# tag.net
KiCad netlist of a schematic drawn in EAGLE
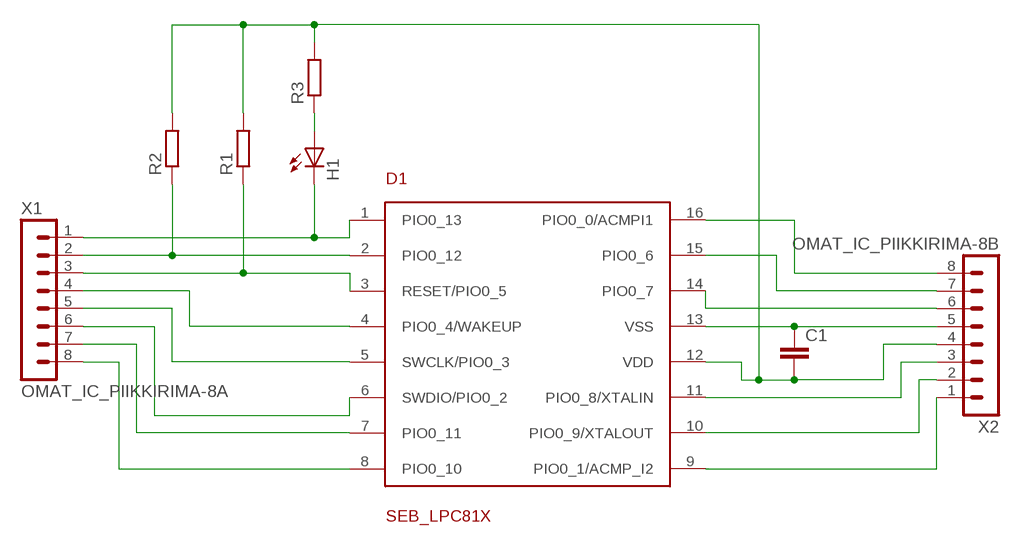
[diagram p0: schematic, sheet 1]

(export (version "E")
  (design (tool "Eeschema 10.0.6"))
  (components
    (comp (ref "C1")
      (value "RCL_C-EUC0603")
      (footprint "eagle-import:RCL_C0603")
      (libsource (lib "eagle-import") (part "RCL_C-EUC0603"))
    )
    (comp (ref "D1")
      (value "SEB_LPC81X")
      (footprint "eagle-import:SEB_TSSOP16")
      (libsource (lib "eagle-import") (part "SEB_LPC81X"))
    )
    (comp (ref "H1")
      (value "OMAT_IC_LEDCHIP-LED0603")
      (footprint "eagle-import:OMAT_IC_CHIP-LED0603")
      (libsource (lib "eagle-import") (part "OMAT_IC_LEDCHIP-LED0603"))
    )
    (comp (ref "R1")
      (value "RCL_R-EU_R0603")
      (footprint "eagle-import:RCL_R0603")
      (libsource (lib "eagle-import") (part "RCL_R-EU_R0603"))
    )
    (comp (ref "R2")
      (value "RCL_R-EU_R0603")
      (footprint "eagle-import:RCL_R0603")
      (libsource (lib "eagle-import") (part "RCL_R-EU_R0603"))
    )
    (comp (ref "R3")
      (value "RCL_R-EU_R0603")
      (footprint "eagle-import:RCL_R0603")
      (libsource (lib "eagle-import") (part "RCL_R-EU_R0603"))
    )
    (comp (ref "X1")
      (value "OMAT_IC_PIIKKIRIMA-8A")
      (footprint "eagle-import:OMAT_IC_PIIKKIRIMA-8")
      (libsource (lib "eagle-import") (part "OMAT_IC_PIIKKIRIMA-8A"))
    )
    (comp (ref "X2")
      (value "OMAT_IC_PIIKKIRIMA-8B")
      (footprint "eagle-import:OMAT_IC_PIIKKIRIMA-8_2")
      (libsource (lib "eagle-import") (part "OMAT_IC_PIIKKIRIMA-8B"))
    )
  )
  (nets
    (net (code "1") (name "Net-(D1-PIO0_0{slash}ACMPI1)") (class "Default")
      (node (ref "D1") (pin "16") (pinfunction "PIO0_0/ACMPI1_16") (pintype "bidirectional"))
      (node (ref "X2") (pin "8") (pinfunction "8_8") (pintype "passive"))
    )
    (net (code "2") (name "Net-(D1-PIO0_1{slash}ACMP_I2)") (class "Default")
      (node (ref "D1") (pin "9") (pinfunction "PIO0_1/ACMP_I2_9") (pintype "bidirectional"))
      (node (ref "X2") (pin "1") (pinfunction "1_1") (pintype "passive"))
    )
    (net (code "3") (name "Net-(D1-PIO0_4{slash}WAKEUP)") (class "Default")
      (node (ref "D1") (pin "4") (pinfunction "PIO0_4/WAKEUP_4") (pintype "bidirectional"))
      (node (ref "X1") (pin "4") (pinfunction "4_4") (pintype "passive"))
    )
    (net (code "4") (name "Net-(D1-PIO0_6)") (class "Default")
      (node (ref "D1") (pin "15") (pinfunction "PIO0_6_15") (pintype "bidirectional"))
      (node (ref "X2") (pin "7") (pinfunction "7_7") (pintype "passive"))
    )
    (net (code "5") (name "Net-(D1-PIO0_7)") (class "Default")
      (node (ref "D1") (pin "14") (pinfunction "PIO0_7_14") (pintype "bidirectional"))
      (node (ref "X2") (pin "6") (pinfunction "6_6") (pintype "passive"))
    )
    (net (code "6") (name "Net-(D1-PIO0_8{slash}XTALIN)") (class "Default")
      (node (ref "D1") (pin "11") (pinfunction "PIO0_8/XTALIN_11") (pintype "bidirectional"))
      (node (ref "X2") (pin "3") (pinfunction "3_3") (pintype "passive"))
    )
    (net (code "7") (name "Net-(D1-PIO0_9{slash}XTALOUT)") (class "Default")
      (node (ref "D1") (pin "10") (pinfunction "PIO0_9/XTALOUT_10") (pintype "bidirectional"))
      (node (ref "X2") (pin "2") (pinfunction "2_2") (pintype "passive"))
    )
    (net (code "8") (name "Net-(D1-PIO0_10)") (class "Default")
      (node (ref "D1") (pin "8") (pinfunction "PIO0_10_8") (pintype "bidirectional"))
      (node (ref "X1") (pin "8") (pinfunction "8_8") (pintype "passive"))
    )
    (net (code "9") (name "Net-(D1-PIO0_11)") (class "Default")
      (node (ref "D1") (pin "7") (pinfunction "PIO0_11_7") (pintype "bidirectional"))
      (node (ref "X1") (pin "7") (pinfunction "7_7") (pintype "passive"))
    )
    (net (code "10") (name "Net-(D1-PIO0_12)") (class "Default")
      (node (ref "D1") (pin "2") (pinfunction "PIO0_12_2") (pintype "bidirectional"))
      (node (ref "R2") (pin "1") (pinfunction "1_1") (pintype "passive"))
      (node (ref "X1") (pin "2") (pinfunction "2_2") (pintype "passive"))
    )
    (net (code "11") (name "Net-(D1-PIO0_13)") (class "Default")
      (node (ref "D1") (pin "1") (pinfunction "PIO0_13_1") (pintype "bidirectional"))
      (node (ref "H1") (pin "C") (pinfunction "C_C") (pintype "passive"))
      (node (ref "X1") (pin "1") (pinfunction "1_1") (pintype "passive"))
    )
    (net (code "12") (name "Net-(D1-RESET{slash}PIO0_5)") (class "Default")
      (node (ref "D1") (pin "3") (pinfunction "RESET/PIO0_5_3") (pintype "bidirectional"))
      (node (ref "R1") (pin "1") (pinfunction "1_1") (pintype "passive"))
      (node (ref "X1") (pin "3") (pinfunction "3_3") (pintype "passive"))
    )
    (net (code "13") (name "Net-(D1-SWCLK{slash}PIO0_3)") (class "Default")
      (node (ref "D1") (pin "5") (pinfunction "SWCLK/PIO0_3_5") (pintype "bidirectional"))
      (node (ref "X1") (pin "5") (pinfunction "5_5") (pintype "passive"))
    )
    (net (code "14") (name "Net-(D1-SWDIO{slash}PIO0_2)") (class "Default")
      (node (ref "D1") (pin "6") (pinfunction "SWDIO/PIO0_2_6") (pintype "bidirectional"))
      (node (ref "X1") (pin "6") (pinfunction "6_6") (pintype "passive"))
    )
    (net (code "15") (name "Net-(D1-VDD)") (class "Default")
      (node (ref "C1") (pin "2") (pinfunction "2_2") (pintype "passive"))
      (node (ref "D1") (pin "12") (pinfunction "VDD_12") (pintype "bidirectional"))
      (node (ref "R1") (pin "2") (pinfunction "2_2") (pintype "passive"))
      (node (ref "R2") (pin "2") (pinfunction "2_2") (pintype "passive"))
      (node (ref "R3") (pin "2") (pinfunction "2_2") (pintype "passive"))
      (node (ref "X2") (pin "4") (pinfunction "4_4") (pintype "passive"))
    )
    (net (code "16") (name "Net-(D1-VSS)") (class "Default")
      (node (ref "C1") (pin "1") (pinfunction "1_1") (pintype "passive"))
      (node (ref "D1") (pin "13") (pinfunction "VSS_13") (pintype "bidirectional"))
      (node (ref "X2") (pin "5") (pinfunction "5_5") (pintype "passive"))
    )
    (net (code "17") (name "Net-(H1-PadA)") (class "Default")
      (node (ref "H1") (pin "A") (pinfunction "A_A") (pintype "passive"))
      (node (ref "R3") (pin "1") (pinfunction "1_1") (pintype "passive"))
    )
  )
)
